# SCH_learningpcb_2025-04-21.net
KiCad netlist of a schematic drawn in EasyEDA
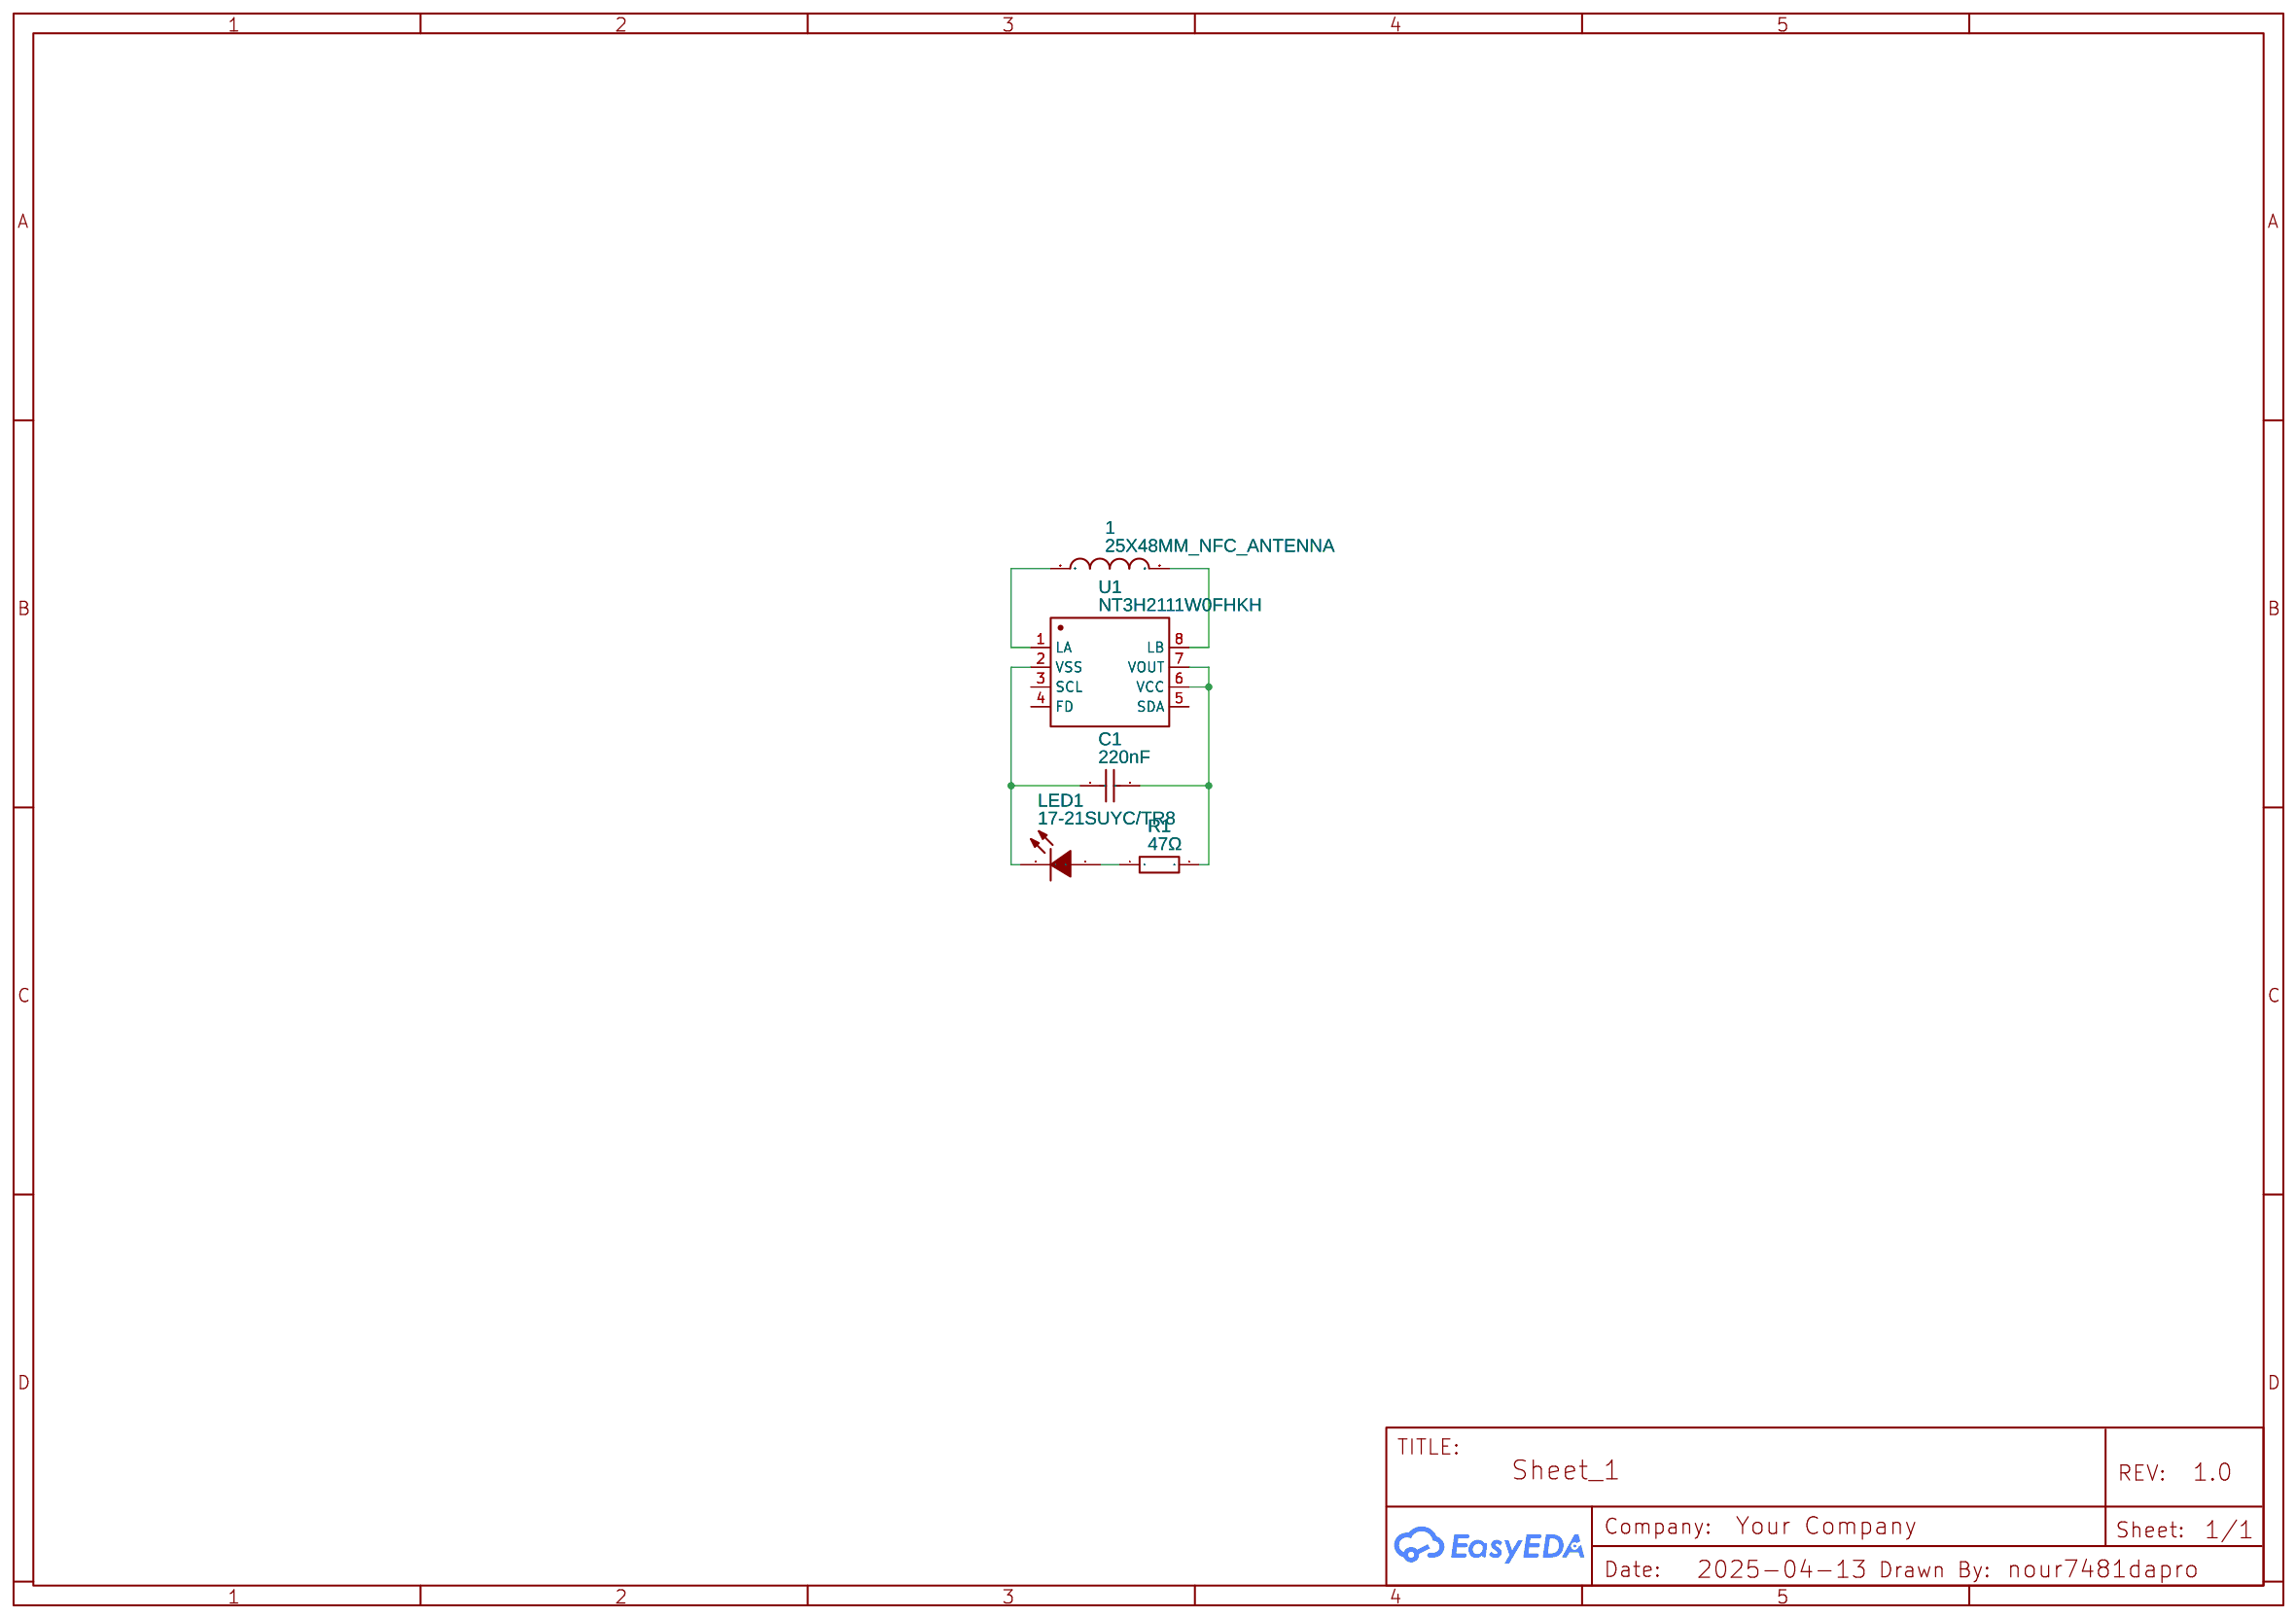
[diagram p0: schematic sheet]

(export (version "E")
  (design (tool "Eeschema 10.0.6"))
  (components
    (comp (ref "1") (value "25X48MM_NFC_ANTENNA") (libsource (lib "") (part "25X48MM_NFC_ANTENNA")))
    (comp (ref "C1")
      (value "220nF")
      (fields
        (field (name "Manufacturer Part") "CL10B224KB8NNNC")
        (field (name "Manufacturer") "SAMSUNG(三星)")
      )
      (libsource (lib "") (part "CL10B224KB8NNNC"))
    )
    (comp (ref "LED1")
      (value "17-21SUYC/TR8")
      (fields (field (name "Manufacturer Part") "KT-0805黄灯") (field (name "Manufacturer") "KENTO"))
      (libsource (lib "") (part "17-21SUYC/TR8"))
    )
    (comp (ref "R1")
      (value "47Ω")
      (fields
        (field (name "Manufacturer Part") "0603WAF470JT5E")
        (field (name "Manufacturer") "UNI-ROYAL(厚声)")
      )
      (libsource (lib "") (part "0603WAF470JT5E"))
    )
    (comp (ref "U1")
      (value "NT3H2111W0FHKH")
      (fields (field (name "Manufacturer") "NXP(恩智浦)"))
      (libsource (lib "") (part "NT3H2111W0FHKH"))
    )
  )
  (nets
    (net (code "1") (name "Net-(LED1-+)") (class "Default")
      (node (ref "LED1") (pin "1") (pinfunction "+_1") (pintype "unspecified"))
      (node (ref "R1") (pin "1") (pinfunction "1_1") (pintype "input"))
    )
    (net (code "2") (name "Net-(LED1--)") (class "Default")
      (node (ref "C1") (pin "1") (pinfunction "1_1") (pintype "input"))
      (node (ref "LED1") (pin "2") (pinfunction "-_2") (pintype "unspecified"))
      (node (ref "U1") (pin "2") (pinfunction "VSS_2") (pintype "unspecified"))
    )
    (net (code "3") (name "Net-(U1-LA)") (class "Default")
      (node (ref "1") (pin "P$1") (pinfunction "P$1_P$1") (pintype "bidirectional"))
      (node (ref "U1") (pin "1") (pinfunction "LA_1") (pintype "unspecified"))
    )
    (net (code "4") (name "Net-(U1-LB)") (class "Default")
      (node (ref "1") (pin "P$2") (pinfunction "P$2_P$2") (pintype "bidirectional"))
      (node (ref "U1") (pin "8") (pinfunction "LB_8") (pintype "unspecified"))
    )
    (net (code "5") (name "Net-(U1-VCC)") (class "Default")
      (node (ref "C1") (pin "2") (pinfunction "2_2") (pintype "input"))
      (node (ref "R1") (pin "2") (pinfunction "2_2") (pintype "input"))
      (node (ref "U1") (pin "6") (pinfunction "VCC_6") (pintype "unspecified"))
      (node (ref "U1") (pin "7") (pinfunction "VOUT_7") (pintype "unspecified"))
    )
    (net (code "6") (name "unconnected-(U1-FD-Pad4)") (class "Default")
      (node (ref "U1") (pin "4") (pinfunction "FD_4") (pintype "unspecified"))
    )
    (net (code "7") (name "unconnected-(U1-SCL-Pad3)") (class "Default")
      (node (ref "U1") (pin "3") (pinfunction "SCL_3") (pintype "unspecified"))
    )
    (net (code "8") (name "unconnected-(U1-SDA-Pad5)") (class "Default")
      (node (ref "U1") (pin "5") (pinfunction "SDA_5") (pintype "unspecified"))
    )
  )
)
